# DIY_tool_-_button_panel_v1.net
KiCad netlist of a schematic drawn in EAGLE
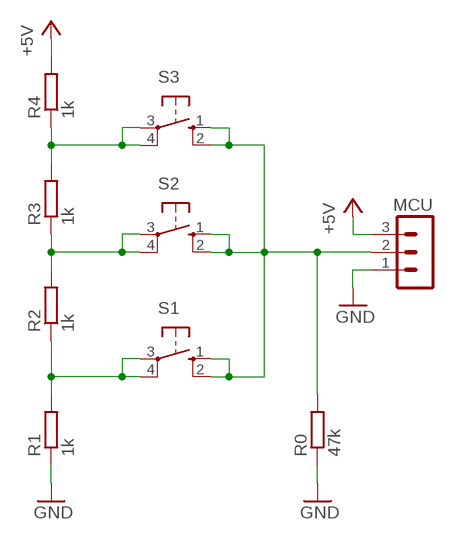
[diagram p0: schematic, sheet 1]

(export (version "E")
  (design (tool "Eeschema 10.0.6"))
  (components
    (comp (ref "MCU")
      (value "MA03-1")
      (footprint "eagle-import:MA03-1")
      (libsource (lib "eagle-import") (part "MA03-1"))
    )
    (comp (ref "R0")
      (value "47k")
      (footprint "eagle-import:0207_10")
      (libsource (lib "eagle-import") (part "R-EU_0207/10"))
    )
    (comp (ref "R1")
      (value "1k")
      (footprint "eagle-import:0207_10")
      (libsource (lib "eagle-import") (part "R-EU_0207/10"))
    )
    (comp (ref "R2")
      (value "1k")
      (footprint "eagle-import:0207_10")
      (libsource (lib "eagle-import") (part "R-EU_0207/10"))
    )
    (comp (ref "R3")
      (value "1k")
      (footprint "eagle-import:0207_10")
      (libsource (lib "eagle-import") (part "R-EU_0207/10"))
    )
    (comp (ref "R4")
      (value "1k")
      (footprint "eagle-import:0207_10")
      (libsource (lib "eagle-import") (part "R-EU_0207/10"))
    )
    (comp (ref "S1")
      (value "10-XX")
      (footprint "eagle-import:B3F-10XX")
      (fields (field (name "MPN") "B3F-1000"))
      (libsource (lib "eagle-import") (part "10-XX"))
    )
    (comp (ref "S2")
      (value "10-XX")
      (footprint "eagle-import:B3F-10XX")
      (fields (field (name "MPN") "B3F-1000"))
      (libsource (lib "eagle-import") (part "10-XX"))
    )
    (comp (ref "S3")
      (value "10-XX")
      (footprint "eagle-import:B3F-10XX")
      (fields (field (name "MPN") "B3F-1000"))
      (libsource (lib "eagle-import") (part "10-XX"))
    )
  )
  (nets
    (net (code "1") (name "+5V") (class "Default")
      (node (ref "MCU") (pin "3") (pinfunction "3_3") (pintype "passive"))
      (node (ref "R4") (pin "2") (pinfunction "2_2") (pintype "passive"))
    )
    (net (code "2") (name "GND") (class "Default")
      (node (ref "MCU") (pin "1") (pinfunction "1_1") (pintype "passive"))
      (node (ref "R0") (pin "1") (pinfunction "1_1") (pintype "passive"))
      (node (ref "R1") (pin "1") (pinfunction "1_1") (pintype "passive"))
    )
    (net (code "3") (name "Net-(S1-P)") (class "Default")
      (node (ref "R1") (pin "2") (pinfunction "2_2") (pintype "passive"))
      (node (ref "R2") (pin "1") (pinfunction "1_1") (pintype "passive"))
      (node (ref "S1") (pin "3") (pinfunction "P_3") (pintype "passive"))
      (node (ref "S1") (pin "4") (pinfunction "P1_4") (pintype "passive"))
    )
    (net (code "4") (name "Net-(S1-S)") (class "Default")
      (node (ref "MCU") (pin "2") (pinfunction "2_2") (pintype "passive"))
      (node (ref "R0") (pin "2") (pinfunction "2_2") (pintype "passive"))
      (node (ref "S1") (pin "1") (pinfunction "S_1") (pintype "passive"))
      (node (ref "S1") (pin "2") (pinfunction "S1_2") (pintype "passive"))
      (node (ref "S2") (pin "1") (pinfunction "S_1") (pintype "passive"))
      (node (ref "S2") (pin "2") (pinfunction "S1_2") (pintype "passive"))
      (node (ref "S3") (pin "1") (pinfunction "S_1") (pintype "passive"))
      (node (ref "S3") (pin "2") (pinfunction "S1_2") (pintype "passive"))
    )
    (net (code "5") (name "Net-(S2-P)") (class "Default")
      (node (ref "R2") (pin "2") (pinfunction "2_2") (pintype "passive"))
      (node (ref "R3") (pin "1") (pinfunction "1_1") (pintype "passive"))
      (node (ref "S2") (pin "3") (pinfunction "P_3") (pintype "passive"))
      (node (ref "S2") (pin "4") (pinfunction "P1_4") (pintype "passive"))
    )
    (net (code "6") (name "Net-(S3-P)") (class "Default")
      (node (ref "R3") (pin "2") (pinfunction "2_2") (pintype "passive"))
      (node (ref "R4") (pin "1") (pinfunction "1_1") (pintype "passive"))
      (node (ref "S3") (pin "3") (pinfunction "P_3") (pintype "passive"))
      (node (ref "S3") (pin "4") (pinfunction "P1_4") (pintype "passive"))
    )
  )
)
